# axiom_beta_plugin_module_1xHDMI_v0_5_53f.net
KiCad netlist of a schematic drawn in EAGLE
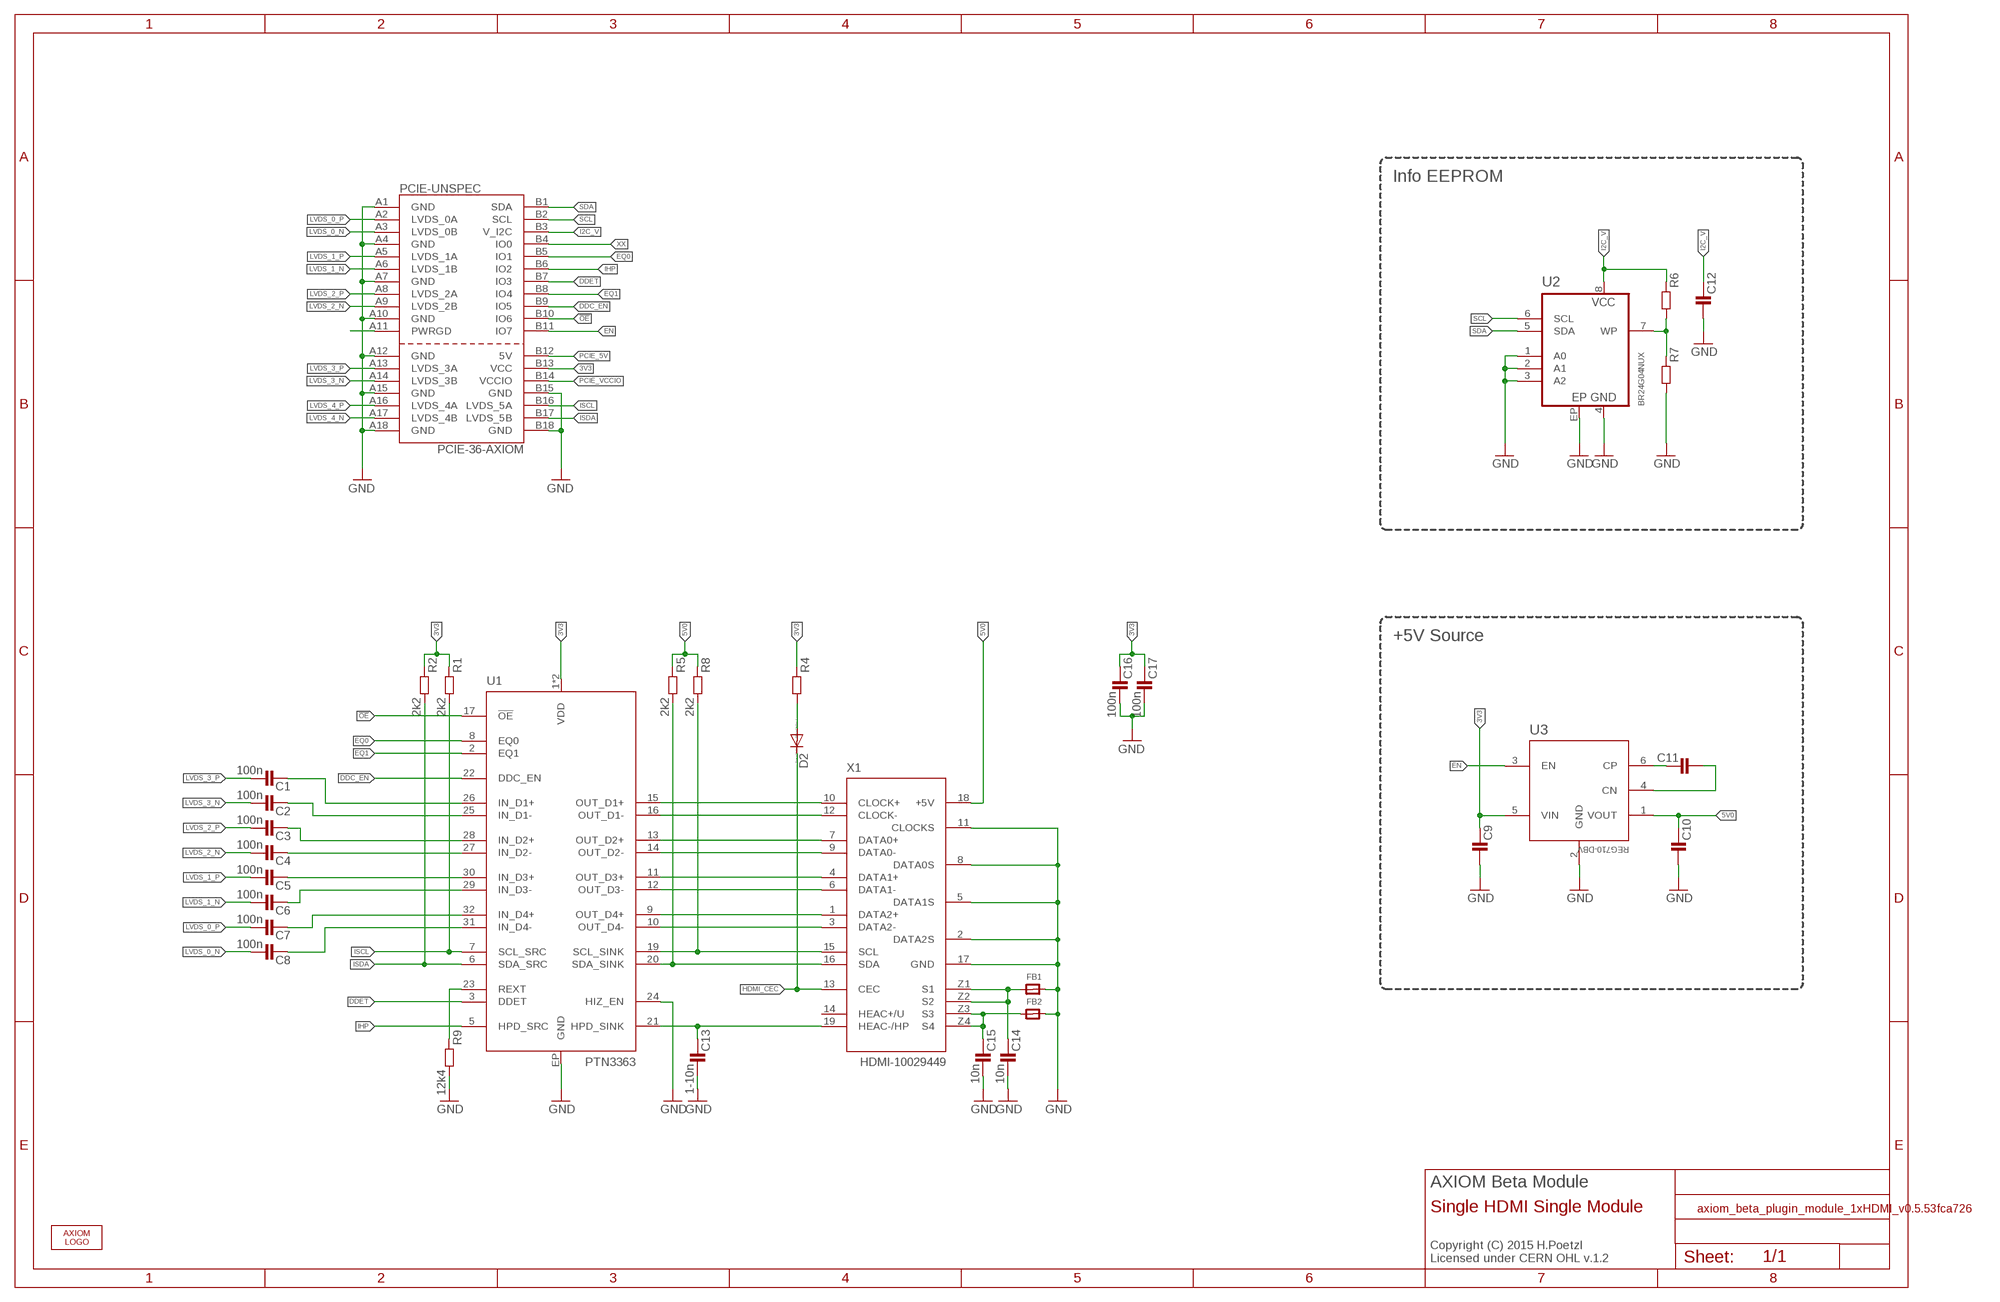
[diagram p0: schematic, sheet 1]

(export (version "E")
  (design (tool "Eeschema 10.0.6"))
  (components
    (comp (ref "C1")
      (value "100n")
      (footprint "eagle-import:0402-C")
      (libsource (lib "eagle-import") (part "C0402-C"))
    )
    (comp (ref "C2")
      (value "100n")
      (footprint "eagle-import:0402-C")
      (libsource (lib "eagle-import") (part "C0402-C"))
    )
    (comp (ref "C3")
      (value "100n")
      (footprint "eagle-import:0402-C")
      (libsource (lib "eagle-import") (part "C0402-C"))
    )
    (comp (ref "C4")
      (value "100n")
      (footprint "eagle-import:0402-C")
      (libsource (lib "eagle-import") (part "C0402-C"))
    )
    (comp (ref "C5")
      (value "100n")
      (footprint "eagle-import:0402-C")
      (libsource (lib "eagle-import") (part "C0402-C"))
    )
    (comp (ref "C6")
      (value "100n")
      (footprint "eagle-import:0402-C")
      (libsource (lib "eagle-import") (part "C0402-C"))
    )
    (comp (ref "C7")
      (value "100n")
      (footprint "eagle-import:0402-C")
      (libsource (lib "eagle-import") (part "C0402-C"))
    )
    (comp (ref "C8")
      (value "100n")
      (footprint "eagle-import:0402-C")
      (libsource (lib "eagle-import") (part "C0402-C"))
    )
    (comp (ref "C9")
      (value "C0603-B")
      (footprint "eagle-import:0603-B")
      (libsource (lib "eagle-import") (part "C0603-B"))
    )
    (comp (ref "C10")
      (value "C0603-B")
      (footprint "eagle-import:0603-B")
      (libsource (lib "eagle-import") (part "C0603-B"))
    )
    (comp (ref "C11")
      (value "C0603-B")
      (footprint "eagle-import:0603-B")
      (libsource (lib "eagle-import") (part "C0603-B"))
    )
    (comp (ref "C12")
      (value "C0402-B")
      (footprint "eagle-import:0402-B")
      (libsource (lib "eagle-import") (part "C0402-B"))
    )
    (comp (ref "C13")
      (value "1-10n")
      (footprint "eagle-import:0402-B")
      (libsource (lib "eagle-import") (part "C0402-B"))
    )
    (comp (ref "C14")
      (value "10n")
      (footprint "eagle-import:0402-B")
      (libsource (lib "eagle-import") (part "C0402-B"))
    )
    (comp (ref "C15")
      (value "10n")
      (footprint "eagle-import:0402-B")
      (libsource (lib "eagle-import") (part "C0402-B"))
    )
    (comp (ref "C16")
      (value "100n")
      (footprint "eagle-import:0402-B")
      (libsource (lib "eagle-import") (part "C0402-B"))
    )
    (comp (ref "C17")
      (value "100n")
      (footprint "eagle-import:0402-B")
      (libsource (lib "eagle-import") (part "C0402-B"))
    )
    (comp (ref "D2")
      (value "DIODE-SOD523")
      (footprint "eagle-import:SOD523")
      (libsource (lib "eagle-import") (part "DIODE-SOD523"))
    )
    (comp (ref "FB1")
      (value "FERRITE_0603MP")
      (footprint "eagle-import:_0603MP")
      (libsource (lib "eagle-import") (part "FERRITE_0603MP"))
    )
    (comp (ref "FB2")
      (value "FERRITE_0603MP")
      (footprint "eagle-import:_0603MP")
      (libsource (lib "eagle-import") (part "FERRITE_0603MP"))
    )
    (comp (ref "PCIE-UNSPEC")
      (value "PCIE-36-AXIOM")
      (footprint "eagle-import:PCIE-36-AXIOM")
      (libsource (lib "eagle-import") (part "PCIE-36-AXIOM"))
    )
    (comp (ref "R1")
      (value "2k2")
      (footprint "eagle-import:0402-B")
      (libsource (lib "eagle-import") (part "R0402-B"))
    )
    (comp (ref "R2")
      (value "2k2")
      (footprint "eagle-import:0402-B")
      (libsource (lib "eagle-import") (part "R0402-B"))
    )
    (comp (ref "R4")
      (value "R0402-B")
      (footprint "eagle-import:0402-B")
      (libsource (lib "eagle-import") (part "R0402-B"))
    )
    (comp (ref "R5")
      (value "2k2")
      (footprint "eagle-import:0402-B")
      (libsource (lib "eagle-import") (part "R0402-B"))
    )
    (comp (ref "R6")
      (value "R0402-B")
      (footprint "eagle-import:0402-B")
      (libsource (lib "eagle-import") (part "R0402-B"))
    )
    (comp (ref "R7")
      (value "R0402-B")
      (footprint "eagle-import:0402-B")
      (libsource (lib "eagle-import") (part "R0402-B"))
    )
    (comp (ref "R8")
      (value "2k2")
      (footprint "eagle-import:0402-B")
      (libsource (lib "eagle-import") (part "R0402-B"))
    )
    (comp (ref "R9")
      (value "12k4")
      (footprint "eagle-import:0402-B")
      (libsource (lib "eagle-import") (part "R0402-B"))
    )
    (comp (ref "U$1")
      (value "AXIOM_LOGO459X70")
      (footprint "eagle-import:AXIOM_LOGO_459X70")
      (libsource (lib "eagle-import") (part "AXIOM_LOGO459X70"))
    )
    (comp (ref "U1")
      (value "PTN3363")
      (footprint "eagle-import:HVQFN32")
      (libsource (lib "eagle-import") (part "PTN3363"))
    )
    (comp (ref "U2")
      (value "BR24G04NUX")
      (footprint "eagle-import:DFN200X300X100-9N")
      (libsource (lib "eagle-import") (part "BR24G04NUX"))
    )
    (comp (ref "U3")
      (value "REG710-DBV")
      (footprint "eagle-import:DBV")
      (libsource (lib "eagle-import") (part "REG710-DBV"))
    )
    (comp (ref "X1")
      (value "HDMI-10029449")
      (footprint "eagle-import:10029449-X01XLF")
      (libsource (lib "eagle-import") (part "HDMI-10029449"))
    )
  )
  (nets
    (net (code "1") (name "/~{OE}") (class "Default")
      (node (ref "PCIE-UNSPEC") (pin "B10") (pinfunction "IO6_B10") (pintype "passive"))
      (node (ref "U1") (pin "17") (pinfunction "~{OE}_17") (pintype "bidirectional"))
    )
    (net (code "2") (name "3V3") (class "Default")
      (node (ref "C16") (pin "1") (pinfunction "1_1") (pintype "passive"))
      (node (ref "C17") (pin "1") (pinfunction "1_1") (pintype "passive"))
      (node (ref "C9") (pin "1") (pinfunction "1_1") (pintype "passive"))
      (node (ref "PCIE-UNSPEC") (pin "B13") (pinfunction "VCC_B13") (pintype "passive"))
      (node (ref "R1") (pin "1") (pinfunction "1_1") (pintype "passive"))
      (node (ref "R2") (pin "1") (pinfunction "1_1") (pintype "passive"))
      (node (ref "R4") (pin "1") (pinfunction "1_1") (pintype "passive"))
      (node (ref "U1") (pin "1") (pinfunction "VDD_1") (pintype "power_in"))
      (node (ref "U1") (pin "18") (pinfunction "VDD_18") (pintype "power_in"))
      (node (ref "U3") (pin "5") (pinfunction "VIN_5") (pintype "power_in"))
    )
    (net (code "3") (name "5V0") (class "Default")
      (node (ref "C10") (pin "1") (pinfunction "1_1") (pintype "passive"))
      (node (ref "R5") (pin "1") (pinfunction "1_1") (pintype "passive"))
      (node (ref "R8") (pin "1") (pinfunction "1_1") (pintype "passive"))
      (node (ref "U3") (pin "1") (pinfunction "VOUT_1") (pintype "output"))
      (node (ref "X1") (pin "18") (pinfunction "+5V_18") (pintype "power_in"))
    )
    (net (code "4") (name "DDC_EN") (class "Default")
      (node (ref "PCIE-UNSPEC") (pin "B9") (pinfunction "IO5_B9") (pintype "passive"))
      (node (ref "U1") (pin "22") (pinfunction "DDC_EN_22") (pintype "bidirectional"))
    )
    (net (code "5") (name "DDET") (class "Default")
      (node (ref "PCIE-UNSPEC") (pin "B7") (pinfunction "IO3_B7") (pintype "passive"))
      (node (ref "U1") (pin "3") (pinfunction "DDET_3") (pintype "bidirectional"))
    )
    (net (code "6") (name "EN") (class "Default")
      (node (ref "PCIE-UNSPEC") (pin "B11") (pinfunction "IO7_B11") (pintype "passive"))
      (node (ref "U3") (pin "3") (pinfunction "EN_3") (pintype "input"))
    )
    (net (code "7") (name "EQ0") (class "Default")
      (node (ref "PCIE-UNSPEC") (pin "B5") (pinfunction "IO1_B5") (pintype "passive"))
      (node (ref "U1") (pin "8") (pinfunction "EQ0_8") (pintype "bidirectional"))
    )
    (net (code "8") (name "EQ1") (class "Default")
      (node (ref "PCIE-UNSPEC") (pin "B8") (pinfunction "IO4_B8") (pintype "passive"))
      (node (ref "U1") (pin "2") (pinfunction "EQ1_2") (pintype "bidirectional"))
    )
    (net (code "9") (name "GND") (class "Default")
      (node (ref "C10") (pin "2") (pinfunction "2_2") (pintype "passive"))
      (node (ref "C12") (pin "2") (pinfunction "2_2") (pintype "passive"))
      (node (ref "C13") (pin "2") (pinfunction "2_2") (pintype "passive"))
      (node (ref "C14") (pin "2") (pinfunction "2_2") (pintype "passive"))
      (node (ref "C15") (pin "2") (pinfunction "2_2") (pintype "passive"))
      (node (ref "C16") (pin "2") (pinfunction "2_2") (pintype "passive"))
      (node (ref "C17") (pin "2") (pinfunction "2_2") (pintype "passive"))
      (node (ref "C9") (pin "2") (pinfunction "2_2") (pintype "passive"))
      (node (ref "FB1") (pin "2") (pinfunction "P$2_2") (pintype "passive"))
      (node (ref "FB2") (pin "2") (pinfunction "P$2_2") (pintype "passive"))
      (node (ref "PCIE-UNSPEC") (pin "A1") (pinfunction "GND_A1") (pintype "passive"))
      (node (ref "PCIE-UNSPEC") (pin "A10") (pinfunction "GND_A10") (pintype "passive"))
      (node (ref "PCIE-UNSPEC") (pin "A12") (pinfunction "GND_A12") (pintype "passive"))
      (node (ref "PCIE-UNSPEC") (pin "A15") (pinfunction "GND_A15") (pintype "passive"))
      (node (ref "PCIE-UNSPEC") (pin "A18") (pinfunction "GND_A18") (pintype "passive"))
      (node (ref "PCIE-UNSPEC") (pin "A4") (pinfunction "GND_A4") (pintype "passive"))
      (node (ref "PCIE-UNSPEC") (pin "A7") (pinfunction "GND_A7") (pintype "passive"))
      (node (ref "PCIE-UNSPEC") (pin "B15") (pinfunction "GND_B15") (pintype "passive"))
      (node (ref "PCIE-UNSPEC") (pin "B18") (pinfunction "GND_B18") (pintype "passive"))
      (node (ref "R7") (pin "2") (pinfunction "2_2") (pintype "passive"))
      (node (ref "R9") (pin "2") (pinfunction "2_2") (pintype "passive"))
      (node (ref "U1") (pin "24") (pinfunction "HIZ_EN_24") (pintype "bidirectional"))
      (node (ref "U1") (pin "EP") (pinfunction "GND_EP") (pintype "bidirectional"))
      (node (ref "U2") (pin "1") (pinfunction "A0_1") (pintype "input"))
      (node (ref "U2") (pin "2") (pinfunction "A1_2") (pintype "input"))
      (node (ref "U2") (pin "3") (pinfunction "A2_3") (pintype "input"))
      (node (ref "U2") (pin "4") (pinfunction "GND_4") (pintype "passive"))
      (node (ref "U2") (pin "EP") (pinfunction "EP_EP") (pintype "passive"))
      (node (ref "U3") (pin "2") (pinfunction "GND_2") (pintype "passive"))
      (node (ref "X1") (pin "11") (pinfunction "CLOCKS_11") (pintype "power_in"))
      (node (ref "X1") (pin "17") (pinfunction "GND_17") (pintype "bidirectional"))
      (node (ref "X1") (pin "2") (pinfunction "DATA2S_2") (pintype "power_in"))
      (node (ref "X1") (pin "5") (pinfunction "DATA1S_5") (pintype "power_in"))
      (node (ref "X1") (pin "8") (pinfunction "DATA0S_8") (pintype "power_in"))
    )
    (net (code "10") (name "HDMI_CEC") (class "Default")
      (node (ref "D2") (pin "C") (pinfunction "C_C") (pintype "passive"))
      (node (ref "X1") (pin "13") (pinfunction "CEC_13") (pintype "bidirectional"))
    )
    (net (code "11") (name "I2C_V") (class "Default")
      (node (ref "C12") (pin "1") (pinfunction "1_1") (pintype "passive"))
      (node (ref "PCIE-UNSPEC") (pin "B3") (pinfunction "V_I2C_B3") (pintype "passive"))
      (node (ref "R6") (pin "1") (pinfunction "1_1") (pintype "passive"))
      (node (ref "U2") (pin "8") (pinfunction "VCC_8") (pintype "power_in"))
    )
    (net (code "12") (name "IHP") (class "Default")
      (node (ref "PCIE-UNSPEC") (pin "B6") (pinfunction "IO2_B6") (pintype "passive"))
      (node (ref "U1") (pin "5") (pinfunction "HPD_SRC_5") (pintype "bidirectional"))
    )
    (net (code "13") (name "ISCL") (class "Default")
      (node (ref "PCIE-UNSPEC") (pin "B16") (pinfunction "LVDS_5A_B16") (pintype "passive"))
      (node (ref "R1") (pin "2") (pinfunction "2_2") (pintype "passive"))
      (node (ref "U1") (pin "7") (pinfunction "SCL_SRC_7") (pintype "bidirectional"))
    )
    (net (code "14") (name "ISDA") (class "Default")
      (node (ref "PCIE-UNSPEC") (pin "B17") (pinfunction "LVDS_5B_B17") (pintype "passive"))
      (node (ref "R2") (pin "2") (pinfunction "2_2") (pintype "passive"))
      (node (ref "U1") (pin "6") (pinfunction "SDA_SRC_6") (pintype "bidirectional"))
    )
    (net (code "15") (name "LVDS_0_N") (class "Default")
      (node (ref "C8") (pin "2") (pinfunction "2_2") (pintype "passive"))
      (node (ref "PCIE-UNSPEC") (pin "A3") (pinfunction "LVDS_0B_A3") (pintype "passive"))
    )
    (net (code "16") (name "LVDS_0_P") (class "Default")
      (node (ref "C7") (pin "2") (pinfunction "2_2") (pintype "passive"))
      (node (ref "PCIE-UNSPEC") (pin "A2") (pinfunction "LVDS_0A_A2") (pintype "passive"))
    )
    (net (code "17") (name "LVDS_1_N") (class "Default")
      (node (ref "C6") (pin "2") (pinfunction "2_2") (pintype "passive"))
      (node (ref "PCIE-UNSPEC") (pin "A6") (pinfunction "LVDS_1B_A6") (pintype "passive"))
    )
    (net (code "18") (name "LVDS_1_P") (class "Default")
      (node (ref "C5") (pin "2") (pinfunction "2_2") (pintype "passive"))
      (node (ref "PCIE-UNSPEC") (pin "A5") (pinfunction "LVDS_1A_A5") (pintype "passive"))
    )
    (net (code "19") (name "LVDS_2_N") (class "Default")
      (node (ref "C4") (pin "2") (pinfunction "2_2") (pintype "passive"))
      (node (ref "PCIE-UNSPEC") (pin "A9") (pinfunction "LVDS_2B_A9") (pintype "passive"))
    )
    (net (code "20") (name "LVDS_2_P") (class "Default")
      (node (ref "C3") (pin "2") (pinfunction "2_2") (pintype "passive"))
      (node (ref "PCIE-UNSPEC") (pin "A8") (pinfunction "LVDS_2A_A8") (pintype "passive"))
    )
    (net (code "21") (name "LVDS_3_N") (class "Default")
      (node (ref "C2") (pin "2") (pinfunction "2_2") (pintype "passive"))
      (node (ref "PCIE-UNSPEC") (pin "A14") (pinfunction "LVDS_3B_A14") (pintype "passive"))
    )
    (net (code "22") (name "LVDS_3_P") (class "Default")
      (node (ref "C1") (pin "2") (pinfunction "2_2") (pintype "passive"))
      (node (ref "PCIE-UNSPEC") (pin "A13") (pinfunction "LVDS_3A_A13") (pintype "passive"))
    )
    (net (code "23") (name "LVDS_4_N") (class "Default")
      (node (ref "PCIE-UNSPEC") (pin "A17") (pinfunction "LVDS_4B_A17") (pintype "passive"))
    )
    (net (code "24") (name "LVDS_4_P") (class "Default")
      (node (ref "PCIE-UNSPEC") (pin "A16") (pinfunction "LVDS_4A_A16") (pintype "passive"))
    )
    (net (code "25") (name "Net-(D2-PadA)") (class "Default")
      (node (ref "D2") (pin "A") (pinfunction "A_A") (pintype "passive"))
      (node (ref "R4") (pin "2") (pinfunction "2_2") (pintype "passive"))
    )
    (net (code "26") (name "Net-(FB1-P$1)") (class "Default")
      (node (ref "C14") (pin "1") (pinfunction "1_1") (pintype "passive"))
      (node (ref "FB1") (pin "1") (pinfunction "P$1_1") (pintype "passive"))
      (node (ref "X1") (pin "Z1") (pinfunction "S1_Z1") (pintype "power_in"))
      (node (ref "X1") (pin "Z2") (pinfunction "S2_Z2") (pintype "power_in"))
    )
    (net (code "27") (name "Net-(FB2-P$1)") (class "Default")
      (node (ref "C15") (pin "1") (pinfunction "1_1") (pintype "passive"))
      (node (ref "FB2") (pin "1") (pinfunction "P$1_1") (pintype "passive"))
      (node (ref "X1") (pin "Z3") (pinfunction "S3_Z3") (pintype "power_in"))
      (node (ref "X1") (pin "Z4") (pinfunction "S4_Z4") (pintype "power_in"))
    )
    (net (code "28") (name "Net-(U1-HPD_SINK)") (class "Default")
      (node (ref "C13") (pin "1") (pinfunction "1_1") (pintype "passive"))
      (node (ref "U1") (pin "21") (pinfunction "HPD_SINK_21") (pintype "bidirectional"))
      (node (ref "X1") (pin "19") (pinfunction "HEAC-/HP_19") (pintype "bidirectional"))
    )
    (net (code "29") (name "Net-(U1-IN_D1+)") (class "Default")
      (node (ref "C1") (pin "1") (pinfunction "1_1") (pintype "passive"))
      (node (ref "U1") (pin "26") (pinfunction "IN_D1+_26") (pintype "bidirectional"))
    )
    (net (code "30") (name "Net-(U1-IN_D1-)") (class "Default")
      (node (ref "C2") (pin "1") (pinfunction "1_1") (pintype "passive"))
      (node (ref "U1") (pin "25") (pinfunction "IN_D1-_25") (pintype "bidirectional"))
    )
    (net (code "31") (name "Net-(U1-IN_D2+)") (class "Default")
      (node (ref "C3") (pin "1") (pinfunction "1_1") (pintype "passive"))
      (node (ref "U1") (pin "28") (pinfunction "IN_D2+_28") (pintype "bidirectional"))
    )
    (net (code "32") (name "Net-(U1-IN_D2-)") (class "Default")
      (node (ref "C4") (pin "1") (pinfunction "1_1") (pintype "passive"))
      (node (ref "U1") (pin "27") (pinfunction "IN_D2-_27") (pintype "bidirectional"))
    )
    (net (code "33") (name "Net-(U1-IN_D3+)") (class "Default")
      (node (ref "C5") (pin "1") (pinfunction "1_1") (pintype "passive"))
      (node (ref "U1") (pin "30") (pinfunction "IN_D3+_30") (pintype "bidirectional"))
    )
    (net (code "34") (name "Net-(U1-IN_D3-)") (class "Default")
      (node (ref "C6") (pin "1") (pinfunction "1_1") (pintype "passive"))
      (node (ref "U1") (pin "29") (pinfunction "IN_D3-_29") (pintype "bidirectional"))
    )
    (net (code "35") (name "Net-(U1-IN_D4+)") (class "Default")
      (node (ref "C7") (pin "1") (pinfunction "1_1") (pintype "passive"))
      (node (ref "U1") (pin "32") (pinfunction "IN_D4+_32") (pintype "bidirectional"))
    )
    (net (code "36") (name "Net-(U1-IN_D4-)") (class "Default")
      (node (ref "C8") (pin "1") (pinfunction "1_1") (pintype "passive"))
      (node (ref "U1") (pin "31") (pinfunction "IN_D4-_31") (pintype "bidirectional"))
    )
    (net (code "37") (name "Net-(U1-OUT_D1+)") (class "Default")
      (node (ref "U1") (pin "15") (pinfunction "OUT_D1+_15") (pintype "bidirectional"))
      (node (ref "X1") (pin "10") (pinfunction "CLOCK+_10") (pintype "bidirectional"))
    )
    (net (code "38") (name "Net-(U1-OUT_D1-)") (class "Default")
      (node (ref "U1") (pin "16") (pinfunction "OUT_D1-_16") (pintype "bidirectional"))
      (node (ref "X1") (pin "12") (pinfunction "CLOCK-_12") (pintype "bidirectional"))
    )
    (net (code "39") (name "Net-(U1-OUT_D2+)") (class "Default")
      (node (ref "U1") (pin "13") (pinfunction "OUT_D2+_13") (pintype "bidirectional"))
      (node (ref "X1") (pin "7") (pinfunction "DATA0+_7") (pintype "bidirectional"))
    )
    (net (code "40") (name "Net-(U1-OUT_D2-)") (class "Default")
      (node (ref "U1") (pin "14") (pinfunction "OUT_D2-_14") (pintype "bidirectional"))
      (node (ref "X1") (pin "9") (pinfunction "DATA0-_9") (pintype "bidirectional"))
    )
    (net (code "41") (name "Net-(U1-OUT_D3+)") (class "Default")
      (node (ref "U1") (pin "11") (pinfunction "OUT_D3+_11") (pintype "bidirectional"))
      (node (ref "X1") (pin "4") (pinfunction "DATA1+_4") (pintype "bidirectional"))
    )
    (net (code "42") (name "Net-(U1-OUT_D3-)") (class "Default")
      (node (ref "U1") (pin "12") (pinfunction "OUT_D3-_12") (pintype "bidirectional"))
      (node (ref "X1") (pin "6") (pinfunction "DATA1-_6") (pintype "bidirectional"))
    )
    (net (code "43") (name "Net-(U1-OUT_D4+)") (class "Default")
      (node (ref "U1") (pin "9") (pinfunction "OUT_D4+_9") (pintype "bidirectional"))
      (node (ref "X1") (pin "1") (pinfunction "DATA2+_1") (pintype "bidirectional"))
    )
    (net (code "44") (name "Net-(U1-OUT_D4-)") (class "Default")
      (node (ref "U1") (pin "10") (pinfunction "OUT_D4-_10") (pintype "bidirectional"))
      (node (ref "X1") (pin "3") (pinfunction "DATA2-_3") (pintype "bidirectional"))
    )
    (net (code "45") (name "Net-(U1-REXT)") (class "Default")
      (node (ref "R9") (pin "1") (pinfunction "1_1") (pintype "passive"))
      (node (ref "U1") (pin "23") (pinfunction "REXT_23") (pintype "bidirectional"))
    )
    (net (code "46") (name "Net-(U1-SCL_SINK)") (class "Default")
      (node (ref "R8") (pin "2") (pinfunction "2_2") (pintype "passive"))
      (node (ref "U1") (pin "19") (pinfunction "SCL_SINK_19") (pintype "bidirectional"))
      (node (ref "X1") (pin "15") (pinfunction "SCL_15") (pintype "bidirectional"))
    )
    (net (code "47") (name "Net-(U1-SDA_SINK)") (class "Default")
      (node (ref "R5") (pin "2") (pinfunction "2_2") (pintype "passive"))
      (node (ref "U1") (pin "20") (pinfunction "SDA_SINK_20") (pintype "bidirectional"))
      (node (ref "X1") (pin "16") (pinfunction "SDA_16") (pintype "bidirectional"))
    )
    (net (code "48") (name "Net-(U2-WP)") (class "Default")
      (node (ref "R6") (pin "2") (pinfunction "2_2") (pintype "passive"))
      (node (ref "R7") (pin "1") (pinfunction "1_1") (pintype "passive"))
      (node (ref "U2") (pin "7") (pinfunction "WP_7") (pintype "input"))
    )
    (net (code "49") (name "Net-(U3-CN)") (class "Default")
      (node (ref "C11") (pin "2") (pinfunction "2_2") (pintype "passive"))
      (node (ref "U3") (pin "4") (pinfunction "CN_4") (pintype "power_in"))
    )
    (net (code "50") (name "Net-(U3-CP)") (class "Default")
      (node (ref "C11") (pin "1") (pinfunction "1_1") (pintype "passive"))
      (node (ref "U3") (pin "6") (pinfunction "CP_6") (pintype "output"))
    )
    (net (code "51") (name "PCIE_5V") (class "Default")
      (node (ref "PCIE-UNSPEC") (pin "B12") (pinfunction "5V_B12") (pintype "passive"))
    )
    (net (code "52") (name "PCIE_VCCIO") (class "Default")
      (node (ref "PCIE-UNSPEC") (pin "B14") (pinfunction "VCCIO_B14") (pintype "passive"))
    )
    (net (code "53") (name "SCL") (class "Default")
      (node (ref "PCIE-UNSPEC") (pin "B2") (pinfunction "SCL_B2") (pintype "passive"))
      (node (ref "U2") (pin "6") (pinfunction "SCL_6") (pintype "input"))
    )
    (net (code "54") (name "SDA") (class "Default")
      (node (ref "PCIE-UNSPEC") (pin "B1") (pinfunction "SDA_B1") (pintype "passive"))
      (node (ref "U2") (pin "5") (pinfunction "SDA_5") (pintype "bidirectional"))
    )
    (net (code "55") (name "XX") (class "Default")
      (node (ref "PCIE-UNSPEC") (pin "B4") (pinfunction "IO0_B4") (pintype "passive"))
    )
    (net (code "56") (name "unconnected-(PCIE-UNSPEC-PWRGD-PadA11)") (class "Default")
      (node (ref "PCIE-UNSPEC") (pin "A11") (pinfunction "PWRGD_A11") (pintype "passive"))
    )
    (net (code "57") (name "unconnected-(X1-HEAC+{slash}U-Pad14)") (class "Default")
      (node (ref "X1") (pin "14") (pinfunction "HEAC+/U_14") (pintype "bidirectional"))
    )
  )
)
